# max7219-dotmatrix.net
KiCad netlist of a schematic drawn in EAGLE
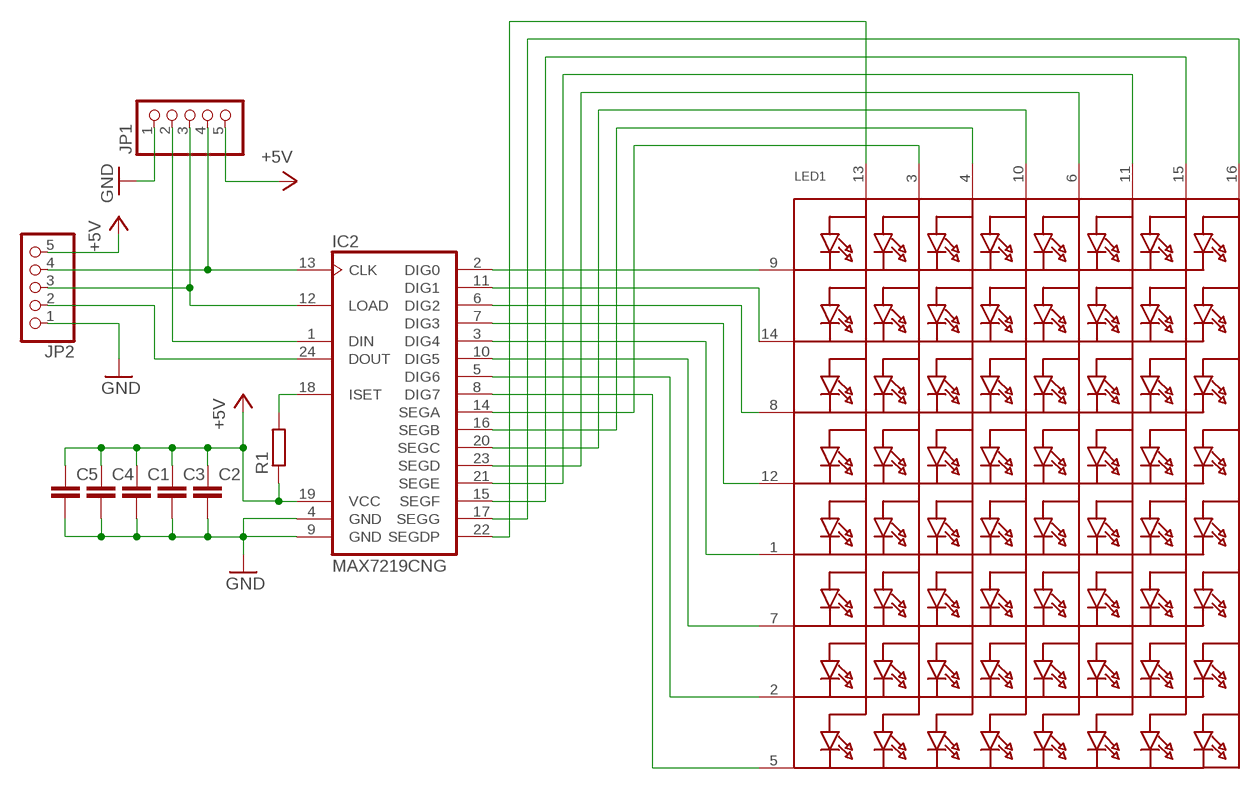
[diagram p0: schematic, sheet 1]

(export (version "E")
  (design (tool "Eeschema 10.0.6"))
  (components
    (comp (ref "C1")
      (value "C-EUC0805K")
      (footprint "eagle-import:C0805K")
      (libsource (lib "eagle-import") (part "C-EUC0805K"))
    )
    (comp (ref "C2")
      (value "C-EUC0805K")
      (footprint "eagle-import:C0805K")
      (libsource (lib "eagle-import") (part "C-EUC0805K"))
    )
    (comp (ref "C3")
      (value "C-EUC0805K")
      (footprint "eagle-import:C0805K")
      (libsource (lib "eagle-import") (part "C-EUC0805K"))
    )
    (comp (ref "C4")
      (value "C-EUC0805K")
      (footprint "eagle-import:C0805K")
      (libsource (lib "eagle-import") (part "C-EUC0805K"))
    )
    (comp (ref "C5")
      (value "C-EUC0805K")
      (footprint "eagle-import:C0805K")
      (libsource (lib "eagle-import") (part "C-EUC0805K"))
    )
    (comp (ref "IC2")
      (value "MAX7219CNG")
      (footprint "eagle-import:DIL24-3")
      (fields (field (name "MF") "MAXIM"))
      (libsource (lib "eagle-import") (part "MAX7219CNG"))
    )
    (comp (ref "JP1")
      (value "PINHD-1X5/90")
      (footprint "eagle-import:1X05_90")
      (libsource (lib "eagle-import") (part "PINHD-1X5/90"))
    )
    (comp (ref "JP2")
      (value "PINHD-1X5/90")
      (footprint "eagle-import:1X05_90")
      (libsource (lib "eagle-import") (part "PINHD-1X5/90"))
    )
    (comp (ref "LED1")
      (value "SEGMENT_8X8_ROWCATHODEM12A881UR")
      (footprint "eagle-import:SEGMENT_BL-M12A881UR")
      (libsource (lib "eagle-import") (part "SEGMENT_8X8_ROWCATHODEM12A881UR"))
    )
    (comp (ref "R1")
      (value "R-EU_M0805")
      (footprint "eagle-import:M0805")
      (libsource (lib "eagle-import") (part "R-EU_M0805"))
    )
  )
  (nets
    (net (code "1") (name "+5V") (class "Default")
      (node (ref "C1") (pin "1") (pinfunction "1_1") (pintype "passive"))
      (node (ref "C2") (pin "1") (pinfunction "1_1") (pintype "passive"))
      (node (ref "C3") (pin "1") (pinfunction "1_1") (pintype "passive"))
      (node (ref "C4") (pin "1") (pinfunction "1_1") (pintype "passive"))
      (node (ref "C5") (pin "1") (pinfunction "1_1") (pintype "passive"))
      (node (ref "IC2") (pin "19") (pinfunction "VCC_19") (pintype "power_in"))
      (node (ref "JP1") (pin "5") (pinfunction "5_5") (pintype "passive"))
      (node (ref "JP2") (pin "5") (pinfunction "5_5") (pintype "passive"))
      (node (ref "R1") (pin "1") (pinfunction "1_1") (pintype "passive"))
    )
    (net (code "2") (name "GND") (class "Default")
      (node (ref "C1") (pin "2") (pinfunction "2_2") (pintype "passive"))
      (node (ref "C2") (pin "2") (pinfunction "2_2") (pintype "passive"))
      (node (ref "C3") (pin "2") (pinfunction "2_2") (pintype "passive"))
      (node (ref "C4") (pin "2") (pinfunction "2_2") (pintype "passive"))
      (node (ref "C5") (pin "2") (pinfunction "2_2") (pintype "passive"))
      (node (ref "IC2") (pin "4") (pinfunction "GND_4") (pintype "power_in"))
      (node (ref "IC2") (pin "9") (pinfunction "GND_9") (pintype "power_in"))
      (node (ref "JP1") (pin "1") (pinfunction "1_1") (pintype "passive"))
      (node (ref "JP2") (pin "1") (pinfunction "1_1") (pintype "passive"))
    )
    (net (code "3") (name "Net-(IC2-CLK)") (class "Default")
      (node (ref "IC2") (pin "13") (pinfunction "CLK_13") (pintype "input"))
      (node (ref "JP1") (pin "4") (pinfunction "4_4") (pintype "passive"))
      (node (ref "JP2") (pin "4") (pinfunction "4_4") (pintype "passive"))
    )
    (net (code "4") (name "Net-(IC2-DIG0)") (class "Default")
      (node (ref "IC2") (pin "2") (pinfunction "DIG0_2") (pintype "output"))
      (node (ref "LED1") (pin "9") (pinfunction "K1_9") (pintype "bidirectional"))
    )
    (net (code "5") (name "Net-(IC2-DIG1)") (class "Default")
      (node (ref "IC2") (pin "11") (pinfunction "DIG1_11") (pintype "output"))
      (node (ref "LED1") (pin "14") (pinfunction "K2_14") (pintype "bidirectional"))
    )
    (net (code "6") (name "Net-(IC2-DIG2)") (class "Default")
      (node (ref "IC2") (pin "6") (pinfunction "DIG2_6") (pintype "output"))
      (node (ref "LED1") (pin "8") (pinfunction "K3_8") (pintype "bidirectional"))
    )
    (net (code "7") (name "Net-(IC2-DIG3)") (class "Default")
      (node (ref "IC2") (pin "7") (pinfunction "DIG3_7") (pintype "output"))
      (node (ref "LED1") (pin "12") (pinfunction "K4_12") (pintype "bidirectional"))
    )
    (net (code "8") (name "Net-(IC2-DIG4)") (class "Default")
      (node (ref "IC2") (pin "3") (pinfunction "DIG4_3") (pintype "output"))
      (node (ref "LED1") (pin "1") (pinfunction "K5_1") (pintype "bidirectional"))
    )
    (net (code "9") (name "Net-(IC2-DIG5)") (class "Default")
      (node (ref "IC2") (pin "10") (pinfunction "DIG5_10") (pintype "output"))
      (node (ref "LED1") (pin "7") (pinfunction "K6_7") (pintype "bidirectional"))
    )
    (net (code "10") (name "Net-(IC2-DIG6)") (class "Default")
      (node (ref "IC2") (pin "5") (pinfunction "DIG6_5") (pintype "output"))
      (node (ref "LED1") (pin "2") (pinfunction "K7_2") (pintype "bidirectional"))
    )
    (net (code "11") (name "Net-(IC2-DIG7)") (class "Default")
      (node (ref "IC2") (pin "8") (pinfunction "DIG7_8") (pintype "output"))
      (node (ref "LED1") (pin "5") (pinfunction "K8_5") (pintype "bidirectional"))
    )
    (net (code "12") (name "Net-(IC2-DIN)") (class "Default")
      (node (ref "IC2") (pin "1") (pinfunction "DIN_1") (pintype "input"))
      (node (ref "JP1") (pin "2") (pinfunction "2_2") (pintype "passive"))
    )
    (net (code "13") (name "Net-(IC2-DOUT)") (class "Default")
      (node (ref "IC2") (pin "24") (pinfunction "DOUT_24") (pintype "output"))
      (node (ref "JP2") (pin "2") (pinfunction "2_2") (pintype "passive"))
    )
    (net (code "14") (name "Net-(IC2-ISET)") (class "Default")
      (node (ref "IC2") (pin "18") (pinfunction "ISET_18") (pintype "input"))
      (node (ref "R1") (pin "2") (pinfunction "2_2") (pintype "passive"))
    )
    (net (code "15") (name "Net-(IC2-LOAD)") (class "Default")
      (node (ref "IC2") (pin "12") (pinfunction "LOAD_12") (pintype "input"))
      (node (ref "JP1") (pin "3") (pinfunction "3_3") (pintype "passive"))
      (node (ref "JP2") (pin "3") (pinfunction "3_3") (pintype "passive"))
    )
    (net (code "16") (name "Net-(IC2-SEGA)") (class "Default")
      (node (ref "IC2") (pin "14") (pinfunction "SEGA_14") (pintype "output"))
      (node (ref "LED1") (pin "3") (pinfunction "A2_3") (pintype "bidirectional"))
    )
    (net (code "17") (name "Net-(IC2-SEGB)") (class "Default")
      (node (ref "IC2") (pin "16") (pinfunction "SEGB_16") (pintype "output"))
      (node (ref "LED1") (pin "4") (pinfunction "A3_4") (pintype "bidirectional"))
    )
    (net (code "18") (name "Net-(IC2-SEGC)") (class "Default")
      (node (ref "IC2") (pin "20") (pinfunction "SEGC_20") (pintype "output"))
      (node (ref "LED1") (pin "10") (pinfunction "A4_10") (pintype "bidirectional"))
    )
    (net (code "19") (name "Net-(IC2-SEGD)") (class "Default")
      (node (ref "IC2") (pin "23") (pinfunction "SEGD_23") (pintype "output"))
      (node (ref "LED1") (pin "6") (pinfunction "A5_6") (pintype "bidirectional"))
    )
    (net (code "20") (name "Net-(IC2-SEGDP)") (class "Default")
      (node (ref "IC2") (pin "22") (pinfunction "SEGDP_22") (pintype "output"))
      (node (ref "LED1") (pin "13") (pinfunction "A1_13") (pintype "bidirectional"))
    )
    (net (code "21") (name "Net-(IC2-SEGE)") (class "Default")
      (node (ref "IC2") (pin "21") (pinfunction "SEGE_21") (pintype "output"))
      (node (ref "LED1") (pin "11") (pinfunction "A6_11") (pintype "bidirectional"))
    )
    (net (code "22") (name "Net-(IC2-SEGF)") (class "Default")
      (node (ref "IC2") (pin "15") (pinfunction "SEGF_15") (pintype "output"))
      (node (ref "LED1") (pin "15") (pinfunction "A7_15") (pintype "bidirectional"))
    )
    (net (code "23") (name "Net-(IC2-SEGG)") (class "Default")
      (node (ref "IC2") (pin "17") (pinfunction "SEGG_17") (pintype "output"))
      (node (ref "LED1") (pin "16") (pinfunction "A8_16") (pintype "bidirectional"))
    )
  )
)
